# -LM1117.net
KiCad netlist of a schematic drawn in Altium Designer
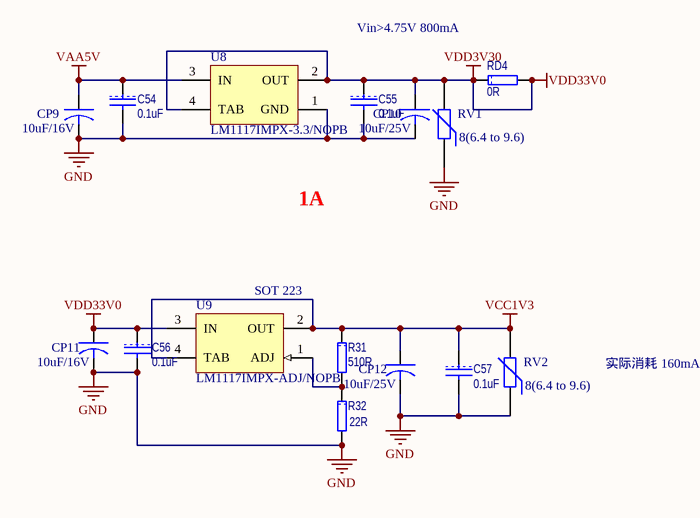
[diagram p0: -LM1117.SchDoc]

(export (version "E")
  (design (tool "Eeschema 10.0.6"))
  (components
    (comp (ref "C54")
      (value "0.1uF")
      (footprint "1608[0603]")
      (description "Capacitor")
      (fields (field (name "MANUFACTURER") "TDK"))
      (libsource (lib "*") (part "CAP"))
    )
    (comp (ref "C55")
      (value "0.1uF")
      (footprint "1608[0603]")
      (description "Capacitor")
      (fields (field (name "MANUFACTURER") "TDK"))
      (libsource (lib "*") (part "CAP"))
    )
    (comp (ref "C56")
      (value "0.1uF")
      (footprint "1608[0603]")
      (description "Capacitor")
      (fields (field (name "MANUFACTURER") "TDK"))
      (libsource (lib "*") (part "CAP"))
    )
    (comp (ref "C57")
      (value "0.1uF")
      (footprint "1608[0603]")
      (description "Capacitor")
      (fields (field (name "MANUFACTURER") "TDK"))
      (libsource (lib "*") (part "CAP"))
    )
    (comp (ref "CP9")
      (value "10uF/16V")
      (footprint "3216[1206]")
      (description "Tantalum Capacitor")
      (libsource (lib "*") (part "CAPACITOR"))
    )
    (comp (ref "CP10")
      (value "10uF/25V")
      (footprint "6032")
      (description "Tantalum Capacitor")
      (libsource (lib "*") (part "CAPACITOR"))
    )
    (comp (ref "CP11")
      (value "10uF/16V")
      (footprint "3216[1206]")
      (description "Tantalum Capacitor")
      (libsource (lib "*") (part "CAPACITOR"))
    )
    (comp (ref "CP12")
      (value "10uF/25V")
      (footprint "6032")
      (description "Tantalum Capacitor")
      (libsource (lib "*") (part "CAPACITOR"))
    )
    (comp (ref "R31")
      (value "510R")
      (footprint "0603R")
      (description "RES")
      (fields (field (name "MANUFACTURER") "vishay"))
      (libsource (lib "*") (part "RES"))
    )
    (comp (ref "R32")
      (value "22R")
      (footprint "0603R")
      (description "RES")
      (fields (field (name "MANUFACTURER") "vishay"))
      (libsource (lib "*") (part "RES"))
    )
    (comp (ref "RD4")
      (value "0R")
      (description "RES")
      (fields (field (name "MANUFACTURER") "vishay"))
      (libsource (lib "*") (part "RES"))
    )
    (comp (ref "RV1")
      (value "8(6.4 to 9.6)")
      (footprint "0603RV")
      (description "压敏电阻")
      (fields (field (name "PUBLISHER") "Altium Limited"))
      (libsource (lib "Miscellaneous Devices") (part "Res Varistor"))
    )
    (comp (ref "RV2")
      (value "8(6.4 to 9.6)")
      (footprint "0603RV")
      (description "压敏电阻")
      (fields (field (name "PUBLISHER") "Altium Limited"))
      (libsource (lib "Miscellaneous Devices") (part "Res Varistor"))
    )
    (comp (ref "U8")
      (value "LM1117IMPX-3.3/NOPB")
      (footprint "MP04A_N")
      (description "800mA Low-Dropout Linear Regulator, 4-pin SOT-223, Pb-Free")
      (fields
        (field (name "PARTNUMBER") "LM1117MPX-3.3/NOPB")
        (field (name "MANUFACTURER") "National Semiconductor")
        (field (name "PUBLISHER") "Altium Limited")
      )
      (libsource (lib "NSC LDO") (part "LM1117MPX-3.3/NOPB"))
    )
    (comp (ref "U9")
      (value "LM1117IMPX-ADJ/NOPB")
      (footprint "MP04A_N")
      (description "800mA Low-Dropout Linear Regulator, 4-pin SOT-223, Pb-Free")
      (fields
        (field (name "PARTNUMBER") "LM1117MPX-ADJ/NOPB")
        (field (name "MANUFACTURER") "National Semiconductor")
        (field (name "PUBLISHER") "Altium Limited")
      )
      (libsource (lib "NSC LDO") (part "LM1117MPX-ADJ/NOPB"))
    )
  )
  (nets
    (net (code "1") (name "GND") (class "Default")
      (node (ref "C54") (pin "2") (pinfunction "2_2") (pintype "passive"))
      (node (ref "C55") (pin "2") (pinfunction "2_2") (pintype "passive"))
      (node (ref "C56") (pin "2") (pinfunction "2_2") (pintype "passive"))
      (node (ref "C57") (pin "2") (pinfunction "2_2") (pintype "passive"))
      (node (ref "CP10") (pin "2") (pinfunction "2_2") (pintype "passive"))
      (node (ref "CP11") (pin "2") (pinfunction "2_2") (pintype "passive"))
      (node (ref "CP12") (pin "2") (pinfunction "2_2") (pintype "passive"))
      (node (ref "CP9") (pin "2") (pinfunction "2_2") (pintype "passive"))
      (node (ref "R32") (pin "2") (pinfunction "2_2") (pintype "passive"))
      (node (ref "RV1") (pin "1") (pinfunction "1_1") (pintype "passive"))
      (node (ref "RV2") (pin "1") (pinfunction "1_1") (pintype "passive"))
      (node (ref "U8") (pin "1") (pinfunction "GND_1") (pintype "power_in"))
    )
    (net (code "2") (name "Net-(U9-ADJ)") (class "Default")
      (node (ref "R31") (pin "2") (pinfunction "2_2") (pintype "passive"))
      (node (ref "R32") (pin "1") (pinfunction "1_1") (pintype "passive"))
      (node (ref "U9") (pin "1") (pinfunction "ADJ_1") (pintype "input"))
    )
    (net (code "3") (name "VAA5V") (class "Default")
      (node (ref "C54") (pin "1") (pinfunction "1_1") (pintype "passive"))
      (node (ref "CP9") (pin "1") (pinfunction "1_1") (pintype "passive"))
      (node (ref "U8") (pin "3") (pinfunction "IN_3") (pintype "power_in"))
    )
    (net (code "4") (name "VCC1V3") (class "Default")
      (node (ref "C57") (pin "1") (pinfunction "1_1") (pintype "passive"))
      (node (ref "CP12") (pin "1") (pinfunction "1_1") (pintype "passive"))
      (node (ref "R31") (pin "1") (pinfunction "1_1") (pintype "passive"))
      (node (ref "RV2") (pin "2") (pinfunction "2_2") (pintype "passive"))
      (node (ref "U9") (pin "2") (pinfunction "OUT_2") (pintype "power_in"))
      (node (ref "U9") (pin "4") (pinfunction "TAB_4") (pintype "power_in"))
    )
    (net (code "5") (name "VDD33V0") (class "Default")
      (node (ref "C55") (pin "1") (pinfunction "1_1") (pintype "passive"))
      (node (ref "C56") (pin "1") (pinfunction "1_1") (pintype "passive"))
      (node (ref "CP10") (pin "1") (pinfunction "1_1") (pintype "passive"))
      (node (ref "CP11") (pin "1") (pinfunction "1_1") (pintype "passive"))
      (node (ref "RD4") (pin "1") (pinfunction "1_1") (pintype "passive"))
      (node (ref "RD4") (pin "2") (pinfunction "2_2") (pintype "passive"))
      (node (ref "RV1") (pin "2") (pinfunction "2_2") (pintype "passive"))
      (node (ref "U8") (pin "2") (pinfunction "OUT_2") (pintype "power_in"))
      (node (ref "U8") (pin "4") (pinfunction "TAB_4") (pintype "power_in"))
      (node (ref "U9") (pin "3") (pinfunction "IN_3") (pintype "power_in"))
    )
  )
)
